# SparkFun_XMega100_Breakout.net
KiCad netlist of a schematic drawn in EAGLE
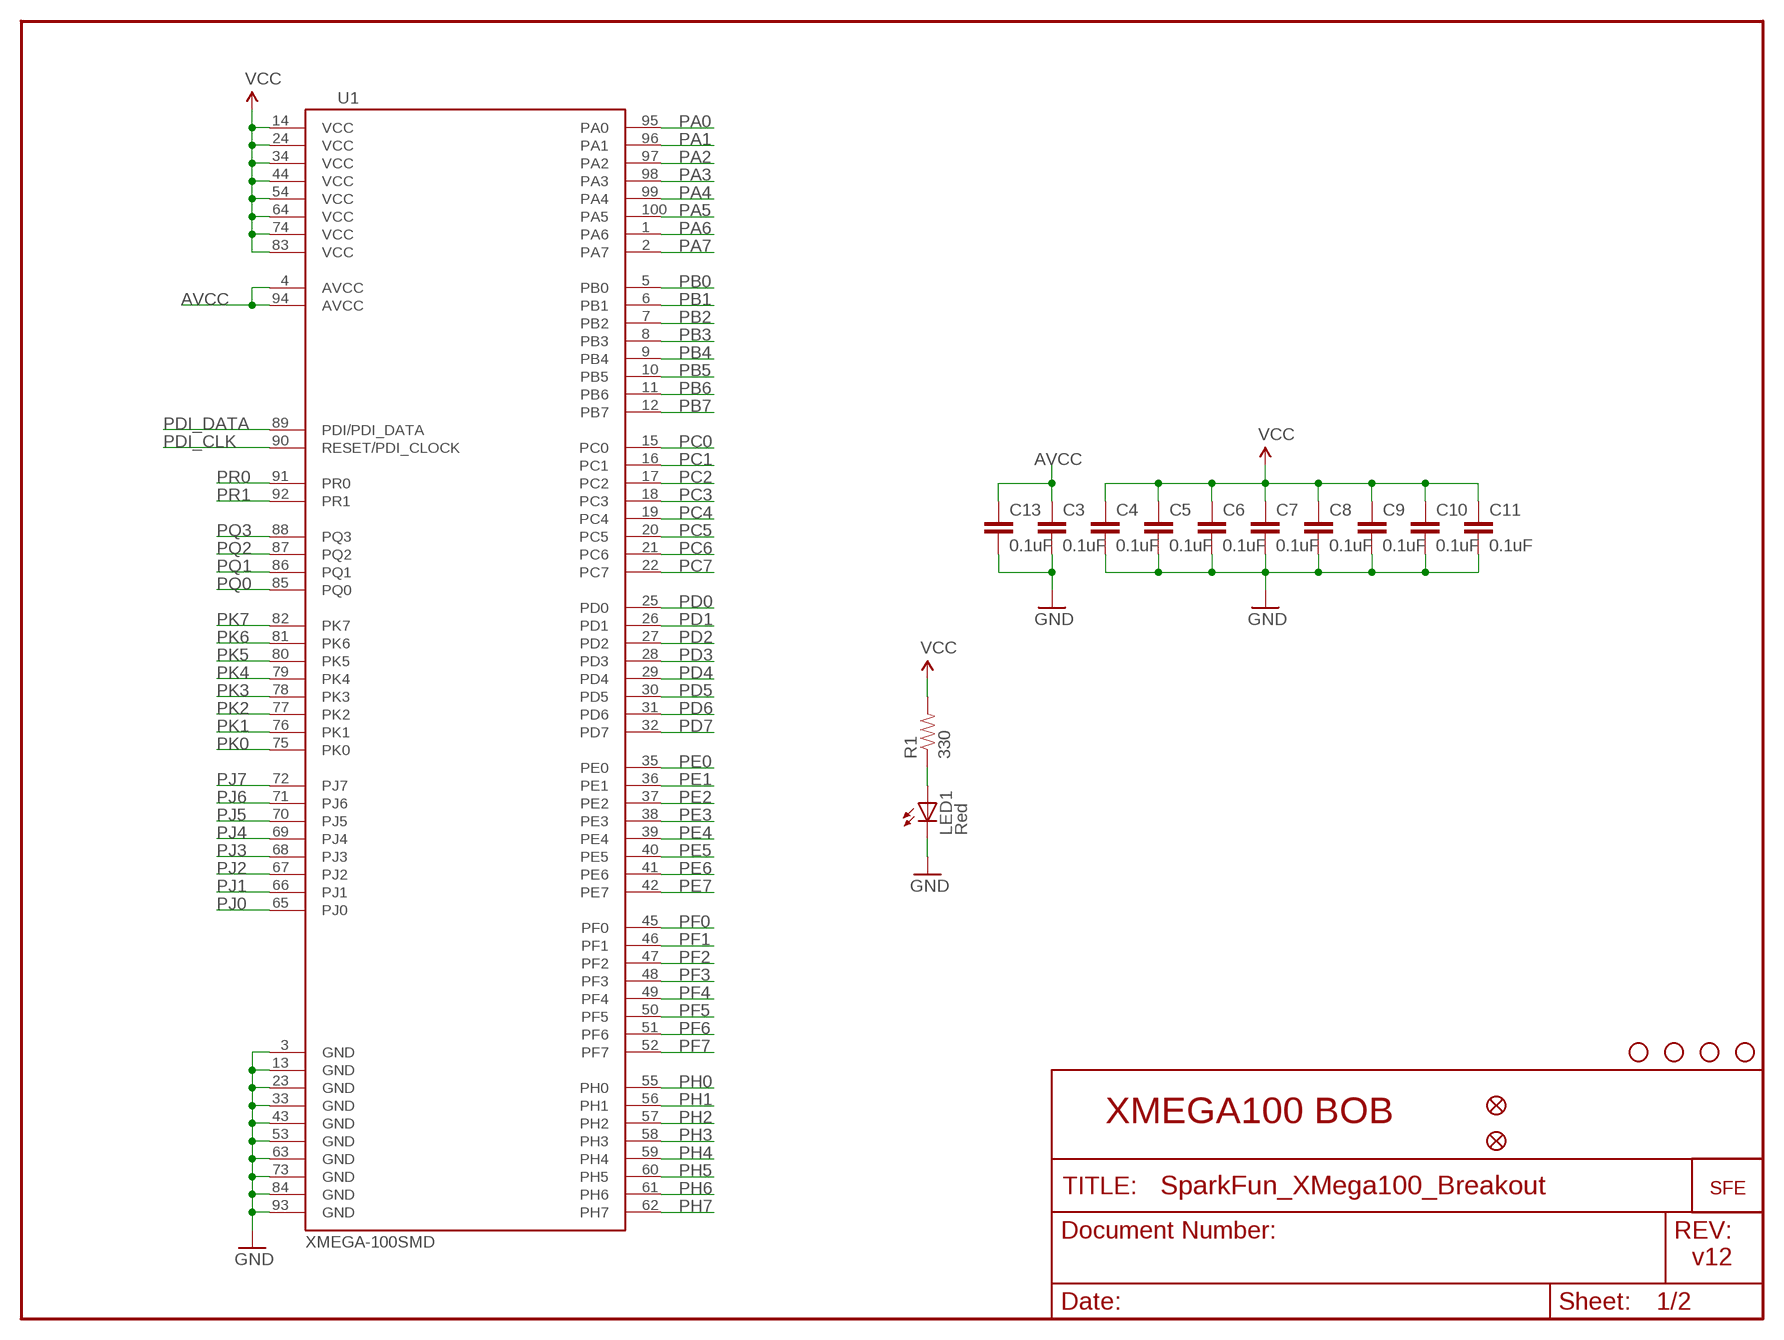
[diagram p0: schematic, sheet 1]
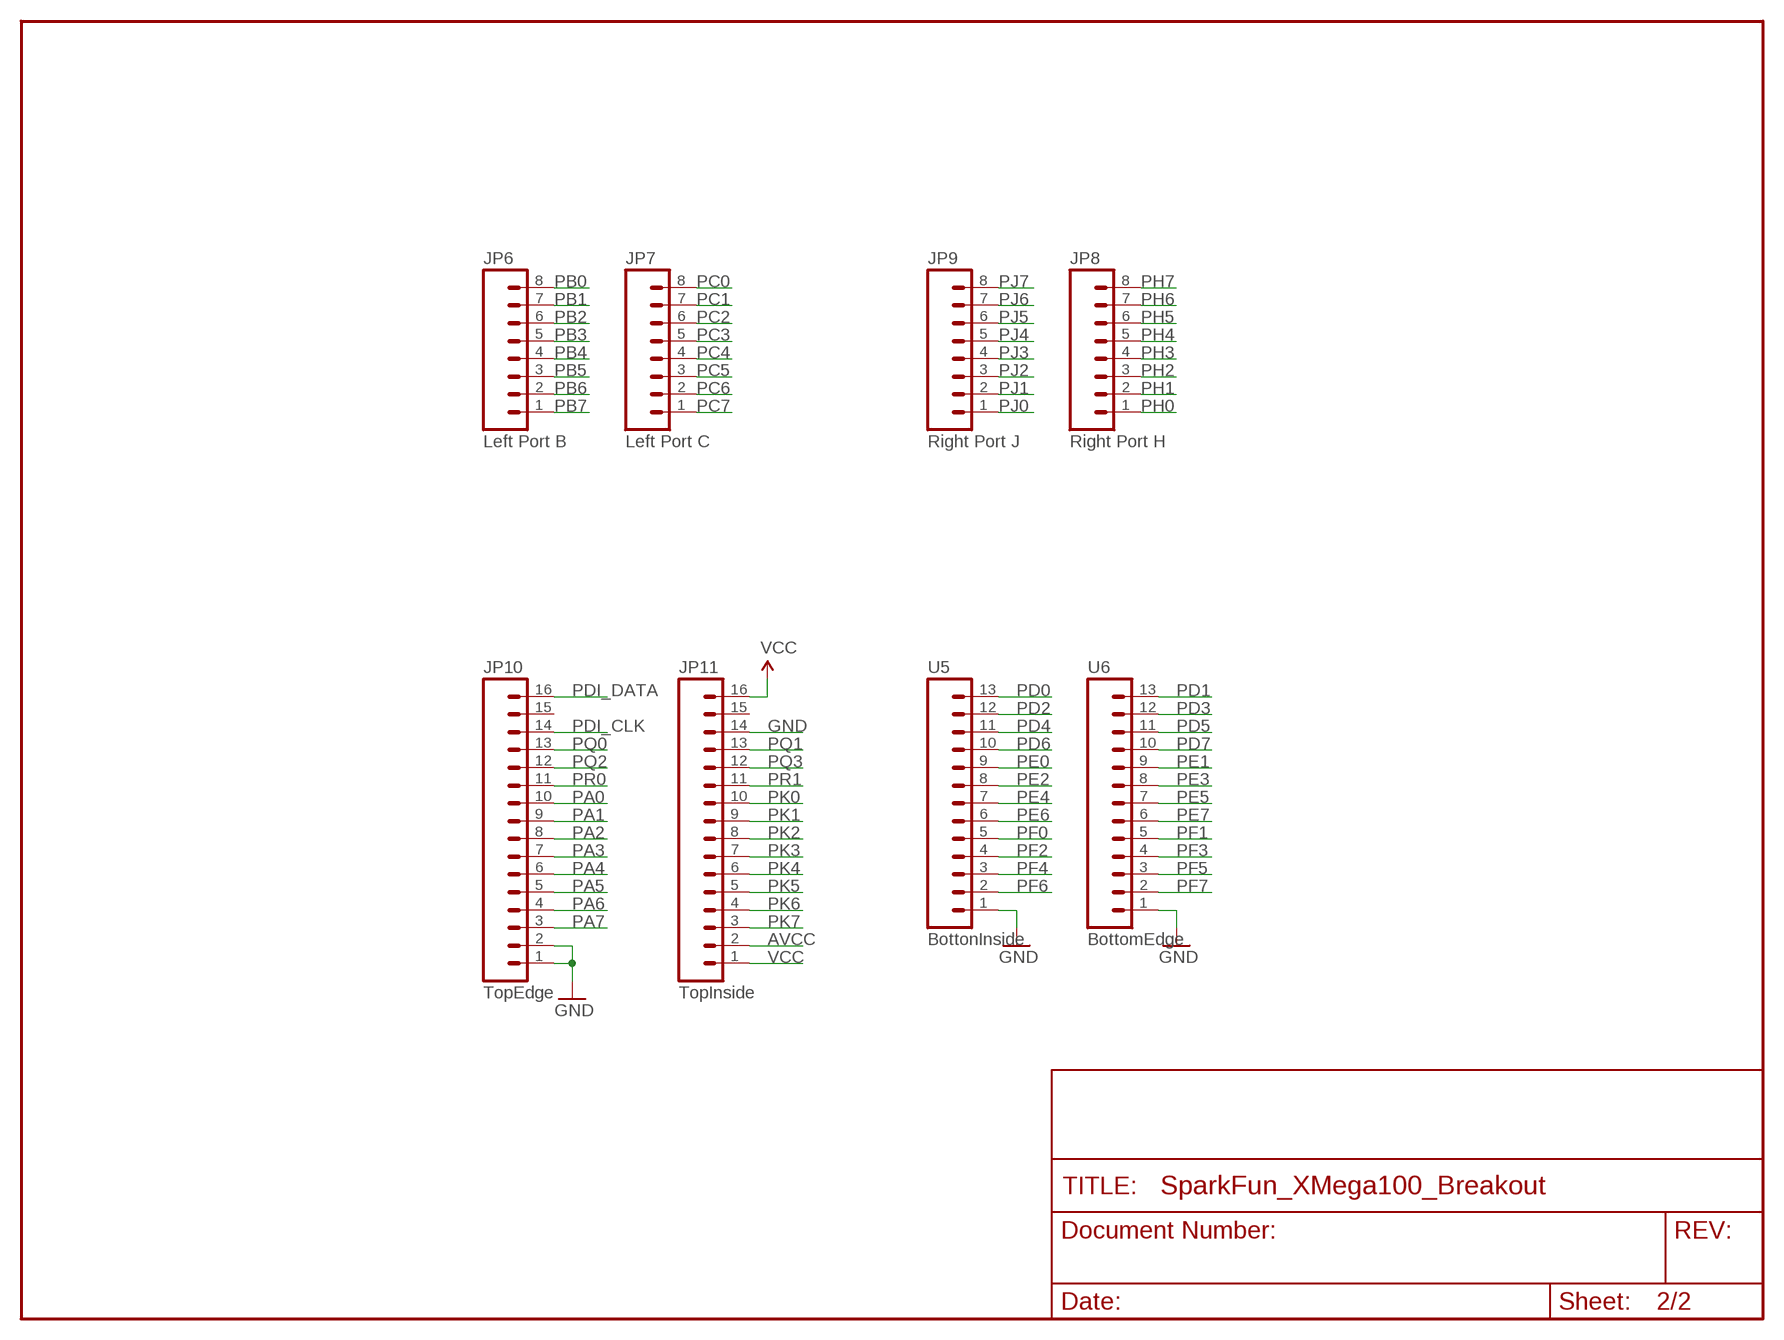
[diagram p1: schematic, sheet 2]

(export (version "E")
  (design (tool "Eeschema 10.0.6"))
  (components
    (comp (ref "JP6")
      (value "Left Port B")
      (footprint "eagle-import:1X08")
      (libsource (lib "eagle-import") (part "M08"))
    )
    (comp (ref "JP7")
      (value "Left Port C")
      (footprint "eagle-import:1X08")
      (libsource (lib "eagle-import") (part "M08"))
    )
    (comp (ref "JP8")
      (value "Right Port H")
      (footprint "eagle-import:1X08")
      (libsource (lib "eagle-import") (part "M08"))
    )
    (comp (ref "JP9")
      (value "Right Port J")
      (footprint "eagle-import:1X08")
      (libsource (lib "eagle-import") (part "M08"))
    )
    (comp (ref "JP10")
      (value "TopEdge")
      (footprint "eagle-import:1X16")
      (libsource (lib "eagle-import") (part "M16PTH"))
    )
    (comp (ref "JP11")
      (value "TopInside")
      (footprint "eagle-import:1X16")
      (libsource (lib "eagle-import") (part "M16PTH"))
    )
    (comp (ref "U5")
      (value "BottonInside")
      (footprint "eagle-import:1X13")
      (libsource (lib "eagle-import") (part "M13"))
    )
    (comp (ref "U6")
      (value "BottomEdge")
      (footprint "eagle-import:1X13")
      (libsource (lib "eagle-import") (part "M13"))
    )
    (comp (ref "C3")
      (value "0.1uF")
      (footprint "eagle-import:0402-CAP")
      (libsource (lib "eagle-import") (part "CAP0402-CAP"))
    )
    (comp (ref "C4")
      (value "0.1uF")
      (footprint "eagle-import:0402-CAP")
      (libsource (lib "eagle-import") (part "CAP0402-CAP"))
    )
    (comp (ref "C5")
      (value "0.1uF")
      (footprint "eagle-import:0402-CAP")
      (libsource (lib "eagle-import") (part "CAP0402-CAP"))
    )
    (comp (ref "C6")
      (value "0.1uF")
      (footprint "eagle-import:0402-CAP")
      (libsource (lib "eagle-import") (part "CAP0402-CAP"))
    )
    (comp (ref "C7")
      (value "0.1uF")
      (footprint "eagle-import:0402-CAP")
      (libsource (lib "eagle-import") (part "CAP0402-CAP"))
    )
    (comp (ref "C8")
      (value "0.1uF")
      (footprint "eagle-import:0402-CAP")
      (libsource (lib "eagle-import") (part "CAP0402-CAP"))
    )
    (comp (ref "C9")
      (value "0.1uF")
      (footprint "eagle-import:0402-CAP")
      (libsource (lib "eagle-import") (part "CAP0402-CAP"))
    )
    (comp (ref "C10")
      (value "0.1uF")
      (footprint "eagle-import:0402-CAP")
      (libsource (lib "eagle-import") (part "CAP0402-CAP"))
    )
    (comp (ref "C11")
      (value "0.1uF")
      (footprint "eagle-import:0402-CAP")
      (libsource (lib "eagle-import") (part "CAP0402-CAP"))
    )
    (comp (ref "C13")
      (value "0.1uF")
      (footprint "eagle-import:0402-CAP")
      (libsource (lib "eagle-import") (part "CAP0402-CAP"))
    )
    (comp (ref "JP1")
      (value "LOGO-SFENEW")
      (footprint "eagle-import:SFE-NEW-WEBLOGO")
      (libsource (lib "eagle-import") (part "LOGO-SFENEW"))
    )
    (comp (ref "JP2")
      (value "STAND-OFF")
      (footprint "eagle-import:STAND-OFF")
      (libsource (lib "eagle-import") (part "STAND-OFF"))
    )
    (comp (ref "JP3")
      (value "STAND-OFF")
      (footprint "eagle-import:STAND-OFF")
      (libsource (lib "eagle-import") (part "STAND-OFF"))
    )
    (comp (ref "JP4")
      (value "STAND-OFF")
      (footprint "eagle-import:STAND-OFF")
      (libsource (lib "eagle-import") (part "STAND-OFF"))
    )
    (comp (ref "JP5")
      (value "STAND-OFF")
      (footprint "eagle-import:STAND-OFF")
      (libsource (lib "eagle-import") (part "STAND-OFF"))
    )
    (comp (ref "JP12")
      (value "FIDUCIAL1X2")
      (footprint "eagle-import:FIDUCIAL-1X2")
      (libsource (lib "eagle-import") (part "FIDUCIAL1X2"))
    )
    (comp (ref "JP13")
      (value "FIDUCIAL1X2")
      (footprint "eagle-import:FIDUCIAL-1X2")
      (libsource (lib "eagle-import") (part "FIDUCIAL1X2"))
    )
    (comp (ref "LED1")
      (value "Red")
      (footprint "eagle-import:LED-0603")
      (libsource (lib "eagle-import") (part "LED0603"))
    )
    (comp (ref "R1")
      (value "330")
      (footprint "eagle-import:0402-RES")
      (libsource (lib "eagle-import") (part "RESISTOR0402-RES"))
    )
    (comp (ref "U1")
      (value "XMEGA-100SMD")
      (footprint "eagle-import:TQFP-100-14X14MM")
      (libsource (lib "eagle-import") (part "XMEGA-100SMD"))
    )
  )
  (nets
    (net (code "1") (name "AVCC") (class "Default")
      (node (ref "C13") (pin "1") (pinfunction "1_1") (pintype "passive"))
      (node (ref "C3") (pin "1") (pinfunction "1_1") (pintype "passive"))
      (node (ref "JP11") (pin "2") (pinfunction "2_2") (pintype "passive"))
      (node (ref "U1") (pin "4") (pinfunction "AVCC_4") (pintype "bidirectional"))
      (node (ref "U1") (pin "94") (pinfunction "AVCC_94") (pintype "bidirectional"))
    )
    (net (code "2") (name "GND") (class "Default")
      (node (ref "C10") (pin "2") (pinfunction "2_2") (pintype "passive"))
      (node (ref "C11") (pin "2") (pinfunction "2_2") (pintype "passive"))
      (node (ref "C13") (pin "2") (pinfunction "2_2") (pintype "passive"))
      (node (ref "C3") (pin "2") (pinfunction "2_2") (pintype "passive"))
      (node (ref "C4") (pin "2") (pinfunction "2_2") (pintype "passive"))
      (node (ref "C5") (pin "2") (pinfunction "2_2") (pintype "passive"))
      (node (ref "C6") (pin "2") (pinfunction "2_2") (pintype "passive"))
      (node (ref "C7") (pin "2") (pinfunction "2_2") (pintype "passive"))
      (node (ref "C8") (pin "2") (pinfunction "2_2") (pintype "passive"))
      (node (ref "C9") (pin "2") (pinfunction "2_2") (pintype "passive"))
      (node (ref "JP10") (pin "1") (pinfunction "1_1") (pintype "passive"))
      (node (ref "JP10") (pin "2") (pinfunction "2_2") (pintype "passive"))
      (node (ref "JP11") (pin "14") (pinfunction "14_14") (pintype "passive"))
      (node (ref "LED1") (pin "C") (pinfunction "C_C") (pintype "passive"))
      (node (ref "U1") (pin "13") (pinfunction "GND_13") (pintype "bidirectional"))
      (node (ref "U1") (pin "23") (pinfunction "GND_23") (pintype "bidirectional"))
      (node (ref "U1") (pin "3") (pinfunction "GND_3") (pintype "bidirectional"))
      (node (ref "U1") (pin "33") (pinfunction "GND_33") (pintype "bidirectional"))
      (node (ref "U1") (pin "43") (pinfunction "GND_43") (pintype "bidirectional"))
      (node (ref "U1") (pin "53") (pinfunction "GND_53") (pintype "bidirectional"))
      (node (ref "U1") (pin "63") (pinfunction "GND_63") (pintype "bidirectional"))
      (node (ref "U1") (pin "73") (pinfunction "GND_73") (pintype "bidirectional"))
      (node (ref "U1") (pin "84") (pinfunction "GND_84") (pintype "bidirectional"))
      (node (ref "U1") (pin "93") (pinfunction "GND_93") (pintype "bidirectional"))
      (node (ref "U5") (pin "1") (pinfunction "1_1") (pintype "passive"))
      (node (ref "U6") (pin "1") (pinfunction "1_1") (pintype "passive"))
    )
    (net (code "3") (name "Net-(LED1-PadA)") (class "Default")
      (node (ref "LED1") (pin "A") (pinfunction "A_A") (pintype "passive"))
      (node (ref "R1") (pin "1") (pinfunction "1_1") (pintype "passive"))
    )
    (net (code "4") (name "PA0") (class "Default")
      (node (ref "JP10") (pin "10") (pinfunction "10_10") (pintype "passive"))
      (node (ref "U1") (pin "95") (pinfunction "PA0_95") (pintype "bidirectional"))
    )
    (net (code "5") (name "PA1") (class "Default")
      (node (ref "JP10") (pin "9") (pinfunction "9_9") (pintype "passive"))
      (node (ref "U1") (pin "96") (pinfunction "PA1_96") (pintype "bidirectional"))
    )
    (net (code "6") (name "PA2") (class "Default")
      (node (ref "JP10") (pin "8") (pinfunction "8_8") (pintype "passive"))
      (node (ref "U1") (pin "97") (pinfunction "PA2_97") (pintype "bidirectional"))
    )
    (net (code "7") (name "PA3") (class "Default")
      (node (ref "JP10") (pin "7") (pinfunction "7_7") (pintype "passive"))
      (node (ref "U1") (pin "98") (pinfunction "PA3_98") (pintype "bidirectional"))
    )
    (net (code "8") (name "PA4") (class "Default")
      (node (ref "JP10") (pin "6") (pinfunction "6_6") (pintype "passive"))
      (node (ref "U1") (pin "99") (pinfunction "PA4_99") (pintype "bidirectional"))
    )
    (net (code "9") (name "PA5") (class "Default")
      (node (ref "JP10") (pin "5") (pinfunction "5_5") (pintype "passive"))
      (node (ref "U1") (pin "100") (pinfunction "PA5_100") (pintype "bidirectional"))
    )
    (net (code "10") (name "PA6") (class "Default")
      (node (ref "JP10") (pin "4") (pinfunction "4_4") (pintype "passive"))
      (node (ref "U1") (pin "1") (pinfunction "PA6_1") (pintype "bidirectional"))
    )
    (net (code "11") (name "PA7") (class "Default")
      (node (ref "JP10") (pin "3") (pinfunction "3_3") (pintype "passive"))
      (node (ref "U1") (pin "2") (pinfunction "PA7_2") (pintype "bidirectional"))
    )
    (net (code "12") (name "PB0") (class "Default")
      (node (ref "JP6") (pin "8") (pinfunction "8_8") (pintype "passive"))
      (node (ref "U1") (pin "5") (pinfunction "PB0_5") (pintype "bidirectional"))
    )
    (net (code "13") (name "PB1") (class "Default")
      (node (ref "JP6") (pin "7") (pinfunction "7_7") (pintype "passive"))
      (node (ref "U1") (pin "6") (pinfunction "PB1_6") (pintype "bidirectional"))
    )
    (net (code "14") (name "PB2") (class "Default")
      (node (ref "JP6") (pin "6") (pinfunction "6_6") (pintype "passive"))
      (node (ref "U1") (pin "7") (pinfunction "PB2_7") (pintype "bidirectional"))
    )
    (net (code "15") (name "PB3") (class "Default")
      (node (ref "JP6") (pin "5") (pinfunction "5_5") (pintype "passive"))
      (node (ref "U1") (pin "8") (pinfunction "PB3_8") (pintype "bidirectional"))
    )
    (net (code "16") (name "PB4") (class "Default")
      (node (ref "JP6") (pin "4") (pinfunction "4_4") (pintype "passive"))
      (node (ref "U1") (pin "9") (pinfunction "PB4_9") (pintype "bidirectional"))
    )
    (net (code "17") (name "PB5") (class "Default")
      (node (ref "JP6") (pin "3") (pinfunction "3_3") (pintype "passive"))
      (node (ref "U1") (pin "10") (pinfunction "PB5_10") (pintype "bidirectional"))
    )
    (net (code "18") (name "PB6") (class "Default")
      (node (ref "JP6") (pin "2") (pinfunction "2_2") (pintype "passive"))
      (node (ref "U1") (pin "11") (pinfunction "PB6_11") (pintype "bidirectional"))
    )
    (net (code "19") (name "PB7") (class "Default")
      (node (ref "JP6") (pin "1") (pinfunction "1_1") (pintype "passive"))
      (node (ref "U1") (pin "12") (pinfunction "PB7_12") (pintype "bidirectional"))
    )
    (net (code "20") (name "PC0") (class "Default")
      (node (ref "JP7") (pin "8") (pinfunction "8_8") (pintype "passive"))
      (node (ref "U1") (pin "15") (pinfunction "PC0_15") (pintype "bidirectional"))
    )
    (net (code "21") (name "PC1") (class "Default")
      (node (ref "JP7") (pin "7") (pinfunction "7_7") (pintype "passive"))
      (node (ref "U1") (pin "16") (pinfunction "PC1_16") (pintype "bidirectional"))
    )
    (net (code "22") (name "PC2") (class "Default")
      (node (ref "JP7") (pin "6") (pinfunction "6_6") (pintype "passive"))
      (node (ref "U1") (pin "17") (pinfunction "PC2_17") (pintype "bidirectional"))
    )
    (net (code "23") (name "PC3") (class "Default")
      (node (ref "JP7") (pin "5") (pinfunction "5_5") (pintype "passive"))
      (node (ref "U1") (pin "18") (pinfunction "PC3_18") (pintype "bidirectional"))
    )
    (net (code "24") (name "PC4") (class "Default")
      (node (ref "JP7") (pin "4") (pinfunction "4_4") (pintype "passive"))
      (node (ref "U1") (pin "19") (pinfunction "PC4_19") (pintype "bidirectional"))
    )
    (net (code "25") (name "PC5") (class "Default")
      (node (ref "JP7") (pin "3") (pinfunction "3_3") (pintype "passive"))
      (node (ref "U1") (pin "20") (pinfunction "PC5_20") (pintype "bidirectional"))
    )
    (net (code "26") (name "PC6") (class "Default")
      (node (ref "JP7") (pin "2") (pinfunction "2_2") (pintype "passive"))
      (node (ref "U1") (pin "21") (pinfunction "PC6_21") (pintype "bidirectional"))
    )
    (net (code "27") (name "PC7") (class "Default")
      (node (ref "JP7") (pin "1") (pinfunction "1_1") (pintype "passive"))
      (node (ref "U1") (pin "22") (pinfunction "PC7_22") (pintype "bidirectional"))
    )
    (net (code "28") (name "PD0") (class "Default")
      (node (ref "U1") (pin "25") (pinfunction "PD0_25") (pintype "bidirectional"))
      (node (ref "U5") (pin "13") (pinfunction "13_13") (pintype "passive"))
    )
    (net (code "29") (name "PD1") (class "Default")
      (node (ref "U1") (pin "26") (pinfunction "PD1_26") (pintype "bidirectional"))
      (node (ref "U6") (pin "13") (pinfunction "13_13") (pintype "passive"))
    )
    (net (code "30") (name "PD2") (class "Default")
      (node (ref "U1") (pin "27") (pinfunction "PD2_27") (pintype "bidirectional"))
      (node (ref "U5") (pin "12") (pinfunction "12_12") (pintype "passive"))
    )
    (net (code "31") (name "PD3") (class "Default")
      (node (ref "U1") (pin "28") (pinfunction "PD3_28") (pintype "bidirectional"))
      (node (ref "U6") (pin "12") (pinfunction "12_12") (pintype "passive"))
    )
    (net (code "32") (name "PD4") (class "Default")
      (node (ref "U1") (pin "29") (pinfunction "PD4_29") (pintype "bidirectional"))
      (node (ref "U5") (pin "11") (pinfunction "11_11") (pintype "passive"))
    )
    (net (code "33") (name "PD5") (class "Default")
      (node (ref "U1") (pin "30") (pinfunction "PD5_30") (pintype "bidirectional"))
      (node (ref "U6") (pin "11") (pinfunction "11_11") (pintype "passive"))
    )
    (net (code "34") (name "PD6") (class "Default")
      (node (ref "U1") (pin "31") (pinfunction "PD6_31") (pintype "bidirectional"))
      (node (ref "U5") (pin "10") (pinfunction "10_10") (pintype "passive"))
    )
    (net (code "35") (name "PD7") (class "Default")
      (node (ref "U1") (pin "32") (pinfunction "PD7_32") (pintype "bidirectional"))
      (node (ref "U6") (pin "10") (pinfunction "10_10") (pintype "passive"))
    )
    (net (code "36") (name "PDI_CLK") (class "Default")
      (node (ref "JP10") (pin "14") (pinfunction "14_14") (pintype "passive"))
      (node (ref "U1") (pin "90") (pinfunction "RESET/PDI_CLOCK_90") (pintype "bidirectional"))
    )
    (net (code "37") (name "PDI_DATA") (class "Default")
      (node (ref "JP10") (pin "16") (pinfunction "16_16") (pintype "passive"))
      (node (ref "U1") (pin "89") (pinfunction "PDI/PDI_DATA_89") (pintype "bidirectional"))
    )
    (net (code "38") (name "PE0") (class "Default")
      (node (ref "U1") (pin "35") (pinfunction "PE0_35") (pintype "bidirectional"))
      (node (ref "U5") (pin "9") (pinfunction "9_9") (pintype "passive"))
    )
    (net (code "39") (name "PE1") (class "Default")
      (node (ref "U1") (pin "36") (pinfunction "PE1_36") (pintype "bidirectional"))
      (node (ref "U6") (pin "9") (pinfunction "9_9") (pintype "passive"))
    )
    (net (code "40") (name "PE2") (class "Default")
      (node (ref "U1") (pin "37") (pinfunction "PE2_37") (pintype "bidirectional"))
      (node (ref "U5") (pin "8") (pinfunction "8_8") (pintype "passive"))
    )
    (net (code "41") (name "PE3") (class "Default")
      (node (ref "U1") (pin "38") (pinfunction "PE3_38") (pintype "bidirectional"))
      (node (ref "U6") (pin "8") (pinfunction "8_8") (pintype "passive"))
    )
    (net (code "42") (name "PE4") (class "Default")
      (node (ref "U1") (pin "39") (pinfunction "PE4_39") (pintype "bidirectional"))
      (node (ref "U5") (pin "7") (pinfunction "7_7") (pintype "passive"))
    )
    (net (code "43") (name "PE5") (class "Default")
      (node (ref "U1") (pin "40") (pinfunction "PE5_40") (pintype "bidirectional"))
      (node (ref "U6") (pin "7") (pinfunction "7_7") (pintype "passive"))
    )
    (net (code "44") (name "PE6") (class "Default")
      (node (ref "U1") (pin "41") (pinfunction "PE6_41") (pintype "bidirectional"))
      (node (ref "U5") (pin "6") (pinfunction "6_6") (pintype "passive"))
    )
    (net (code "45") (name "PE7") (class "Default")
      (node (ref "U1") (pin "42") (pinfunction "PE7_42") (pintype "bidirectional"))
      (node (ref "U6") (pin "6") (pinfunction "6_6") (pintype "passive"))
    )
    (net (code "46") (name "PF0") (class "Default")
      (node (ref "U1") (pin "45") (pinfunction "PF0_45") (pintype "bidirectional"))
      (node (ref "U5") (pin "5") (pinfunction "5_5") (pintype "passive"))
    )
    (net (code "47") (name "PF1") (class "Default")
      (node (ref "U1") (pin "46") (pinfunction "PF1_46") (pintype "bidirectional"))
      (node (ref "U6") (pin "5") (pinfunction "5_5") (pintype "passive"))
    )
    (net (code "48") (name "PF2") (class "Default")
      (node (ref "U1") (pin "47") (pinfunction "PF2_47") (pintype "bidirectional"))
      (node (ref "U5") (pin "4") (pinfunction "4_4") (pintype "passive"))
    )
    (net (code "49") (name "PF3") (class "Default")
      (node (ref "U1") (pin "48") (pinfunction "PF3_48") (pintype "bidirectional"))
      (node (ref "U6") (pin "4") (pinfunction "4_4") (pintype "passive"))
    )
    (net (code "50") (name "PF4") (class "Default")
      (node (ref "U1") (pin "49") (pinfunction "PF4_49") (pintype "bidirectional"))
      (node (ref "U5") (pin "3") (pinfunction "3_3") (pintype "passive"))
    )
    (net (code "51") (name "PF5") (class "Default")
      (node (ref "U1") (pin "50") (pinfunction "PF5_50") (pintype "bidirectional"))
      (node (ref "U6") (pin "3") (pinfunction "3_3") (pintype "passive"))
    )
    (net (code "52") (name "PF6") (class "Default")
      (node (ref "U1") (pin "51") (pinfunction "PF6_51") (pintype "bidirectional"))
      (node (ref "U5") (pin "2") (pinfunction "2_2") (pintype "passive"))
    )
    (net (code "53") (name "PF7") (class "Default")
      (node (ref "U1") (pin "52") (pinfunction "PF7_52") (pintype "bidirectional"))
      (node (ref "U6") (pin "2") (pinfunction "2_2") (pintype "passive"))
    )
    (net (code "54") (name "PH0") (class "Default")
      (node (ref "JP8") (pin "1") (pinfunction "1_1") (pintype "passive"))
      (node (ref "U1") (pin "55") (pinfunction "PH0_55") (pintype "bidirectional"))
    )
    (net (code "55") (name "PH1") (class "Default")
      (node (ref "JP8") (pin "2") (pinfunction "2_2") (pintype "passive"))
      (node (ref "U1") (pin "56") (pinfunction "PH1_56") (pintype "bidirectional"))
    )
    (net (code "56") (name "PH2") (class "Default")
      (node (ref "JP8") (pin "3") (pinfunction "3_3") (pintype "passive"))
      (node (ref "U1") (pin "57") (pinfunction "PH2_57") (pintype "bidirectional"))
    )
    (net (code "57") (name "PH3") (class "Default")
      (node (ref "JP8") (pin "4") (pinfunction "4_4") (pintype "passive"))
      (node (ref "U1") (pin "58") (pinfunction "PH3_58") (pintype "bidirectional"))
    )
    (net (code "58") (name "PH4") (class "Default")
      (node (ref "JP8") (pin "5") (pinfunction "5_5") (pintype "passive"))
      (node (ref "U1") (pin "59") (pinfunction "PH4_59") (pintype "bidirectional"))
    )
    (net (code "59") (name "PH5") (class "Default")
      (node (ref "JP8") (pin "6") (pinfunction "6_6") (pintype "passive"))
      (node (ref "U1") (pin "60") (pinfunction "PH5_60") (pintype "bidirectional"))
    )
    (net (code "60") (name "PH6") (class "Default")
      (node (ref "JP8") (pin "7") (pinfunction "7_7") (pintype "passive"))
      (node (ref "U1") (pin "61") (pinfunction "PH6_61") (pintype "bidirectional"))
    )
    (net (code "61") (name "PH7") (class "Default")
      (node (ref "JP8") (pin "8") (pinfunction "8_8") (pintype "passive"))
      (node (ref "U1") (pin "62") (pinfunction "PH7_62") (pintype "bidirectional"))
    )
    (net (code "62") (name "PJ0") (class "Default")
      (node (ref "JP9") (pin "1") (pinfunction "1_1") (pintype "passive"))
      (node (ref "U1") (pin "65") (pinfunction "PJ0_65") (pintype "bidirectional"))
    )
    (net (code "63") (name "PJ1") (class "Default")
      (node (ref "JP9") (pin "2") (pinfunction "2_2") (pintype "passive"))
      (node (ref "U1") (pin "66") (pinfunction "PJ1_66") (pintype "bidirectional"))
    )
    (net (code "64") (name "PJ2") (class "Default")
      (node (ref "JP9") (pin "3") (pinfunction "3_3") (pintype "passive"))
      (node (ref "U1") (pin "67") (pinfunction "PJ2_67") (pintype "bidirectional"))
    )
    (net (code "65") (name "PJ3") (class "Default")
      (node (ref "JP9") (pin "4") (pinfunction "4_4") (pintype "passive"))
      (node (ref "U1") (pin "68") (pinfunction "PJ3_68") (pintype "bidirectional"))
    )
    (net (code "66") (name "PJ4") (class "Default")
      (node (ref "JP9") (pin "5") (pinfunction "5_5") (pintype "passive"))
      (node (ref "U1") (pin "69") (pinfunction "PJ4_69") (pintype "bidirectional"))
    )
    (net (code "67") (name "PJ5") (class "Default")
      (node (ref "JP9") (pin "6") (pinfunction "6_6") (pintype "passive"))
      (node (ref "U1") (pin "70") (pinfunction "PJ5_70") (pintype "bidirectional"))
    )
    (net (code "68") (name "PJ6") (class "Default")
      (node (ref "JP9") (pin "7") (pinfunction "7_7") (pintype "passive"))
      (node (ref "U1") (pin "71") (pinfunction "PJ6_71") (pintype "bidirectional"))
    )
    (net (code "69") (name "PJ7") (class "Default")
      (node (ref "JP9") (pin "8") (pinfunction "8_8") (pintype "passive"))
      (node (ref "U1") (pin "72") (pinfunction "PJ7_72") (pintype "bidirectional"))
    )
    (net (code "70") (name "PK0") (class "Default")
      (node (ref "JP11") (pin "10") (pinfunction "10_10") (pintype "passive"))
      (node (ref "U1") (pin "75") (pinfunction "PK0_75") (pintype "bidirectional"))
    )
    (net (code "71") (name "PK1") (class "Default")
      (node (ref "JP11") (pin "9") (pinfunction "9_9") (pintype "passive"))
      (node (ref "U1") (pin "76") (pinfunction "PK1_76") (pintype "bidirectional"))
    )
    (net (code "72") (name "PK2") (class "Default")
      (node (ref "JP11") (pin "8") (pinfunction "8_8") (pintype "passive"))
      (node (ref "U1") (pin "77") (pinfunction "PK2_77") (pintype "bidirectional"))
    )
    (net (code "73") (name "PK3") (class "Default")
      (node (ref "JP11") (pin "7") (pinfunction "7_7") (pintype "passive"))
      (node (ref "U1") (pin "78") (pinfunction "PK3_78") (pintype "bidirectional"))
    )
    (net (code "74") (name "PK4") (class "Default")
      (node (ref "JP11") (pin "6") (pinfunction "6_6") (pintype "passive"))
      (node (ref "U1") (pin "79") (pinfunction "PK4_79") (pintype "bidirectional"))
    )
    (net (code "75") (name "PK5") (class "Default")
      (node (ref "JP11") (pin "5") (pinfunction "5_5") (pintype "passive"))
      (node (ref "U1") (pin "80") (pinfunction "PK5_80") (pintype "bidirectional"))
    )
    (net (code "76") (name "PK6") (class "Default")
      (node (ref "JP11") (pin "4") (pinfunction "4_4") (pintype "passive"))
      (node (ref "U1") (pin "81") (pinfunction "PK6_81") (pintype "bidirectional"))
    )
    (net (code "77") (name "PK7") (class "Default")
      (node (ref "JP11") (pin "3") (pinfunction "3_3") (pintype "passive"))
      (node (ref "U1") (pin "82") (pinfunction "PK7_82") (pintype "bidirectional"))
    )
    (net (code "78") (name "PQ0") (class "Default")
      (node (ref "JP10") (pin "13") (pinfunction "13_13") (pintype "passive"))
      (node (ref "U1") (pin "85") (pinfunction "PQ0_85") (pintype "bidirectional"))
    )
    (net (code "79") (name "PQ1") (class "Default")
      (node (ref "JP11") (pin "13") (pinfunction "13_13") (pintype "passive"))
      (node (ref "U1") (pin "86") (pinfunction "PQ1_86") (pintype "bidirectional"))
    )
    (net (code "80") (name "PQ2") (class "Default")
      (node (ref "JP10") (pin "12") (pinfunction "12_12") (pintype "passive"))
      (node (ref "U1") (pin "87") (pinfunction "PQ2_87") (pintype "bidirectional"))
    )
    (net (code "81") (name "PQ3") (class "Default")
      (node (ref "JP11") (pin "12") (pinfunction "12_12") (pintype "passive"))
      (node (ref "U1") (pin "88") (pinfunction "PQ3_88") (pintype "bidirectional"))
    )
    (net (code "82") (name "PR0") (class "Default")
      (node (ref "JP10") (pin "11") (pinfunction "11_11") (pintype "passive"))
      (node (ref "U1") (pin "91") (pinfunction "PR0_91") (pintype "bidirectional"))
    )
    (net (code "83") (name "PR1") (class "Default")
      (node (ref "JP11") (pin "11") (pinfunction "11_11") (pintype "passive"))
      (node (ref "U1") (pin "92") (pinfunction "PR1_92") (pintype "bidirectional"))
    )
    (net (code "84") (name "VCC") (class "Default")
      (node (ref "C10") (pin "1") (pinfunction "1_1") (pintype "passive"))
      (node (ref "C11") (pin "1") (pinfunction "1_1") (pintype "passive"))
      (node (ref "C4") (pin "1") (pinfunction "1_1") (pintype "passive"))
      (node (ref "C5") (pin "1") (pinfunction "1_1") (pintype "passive"))
      (node (ref "C6") (pin "1") (pinfunction "1_1") (pintype "passive"))
      (node (ref "C7") (pin "1") (pinfunction "1_1") (pintype "passive"))
      (node (ref "C8") (pin "1") (pinfunction "1_1") (pintype "passive"))
      (node (ref "C9") (pin "1") (pinfunction "1_1") (pintype "passive"))
      (node (ref "JP11") (pin "1") (pinfunction "1_1") (pintype "passive"))
      (node (ref "JP11") (pin "16") (pinfunction "16_16") (pintype "passive"))
      (node (ref "R1") (pin "2") (pinfunction "2_2") (pintype "passive"))
      (node (ref "U1") (pin "14") (pinfunction "VCC_14") (pintype "bidirectional"))
      (node (ref "U1") (pin "24") (pinfunction "VCC_24") (pintype "bidirectional"))
      (node (ref "U1") (pin "34") (pinfunction "VCC_34") (pintype "bidirectional"))
      (node (ref "U1") (pin "44") (pinfunction "VCC_44") (pintype "bidirectional"))
      (node (ref "U1") (pin "54") (pinfunction "VCC_54") (pintype "bidirectional"))
      (node (ref "U1") (pin "64") (pinfunction "VCC_64") (pintype "bidirectional"))
      (node (ref "U1") (pin "74") (pinfunction "VCC_74") (pintype "bidirectional"))
      (node (ref "U1") (pin "83") (pinfunction "VCC_83") (pintype "bidirectional"))
    )
    (net (code "85") (name "unconnected-(JP10-Pad15)") (class "Default")
      (node (ref "JP10") (pin "15") (pinfunction "15_15") (pintype "passive"))
    )
    (net (code "86") (name "unconnected-(JP11-Pad15)") (class "Default")
      (node (ref "JP11") (pin "15") (pinfunction "15_15") (pintype "passive"))
    )
  )
)
